# ATX_Power_Connector_Breakout.net
KiCad netlist of a schematic drawn in EAGLE
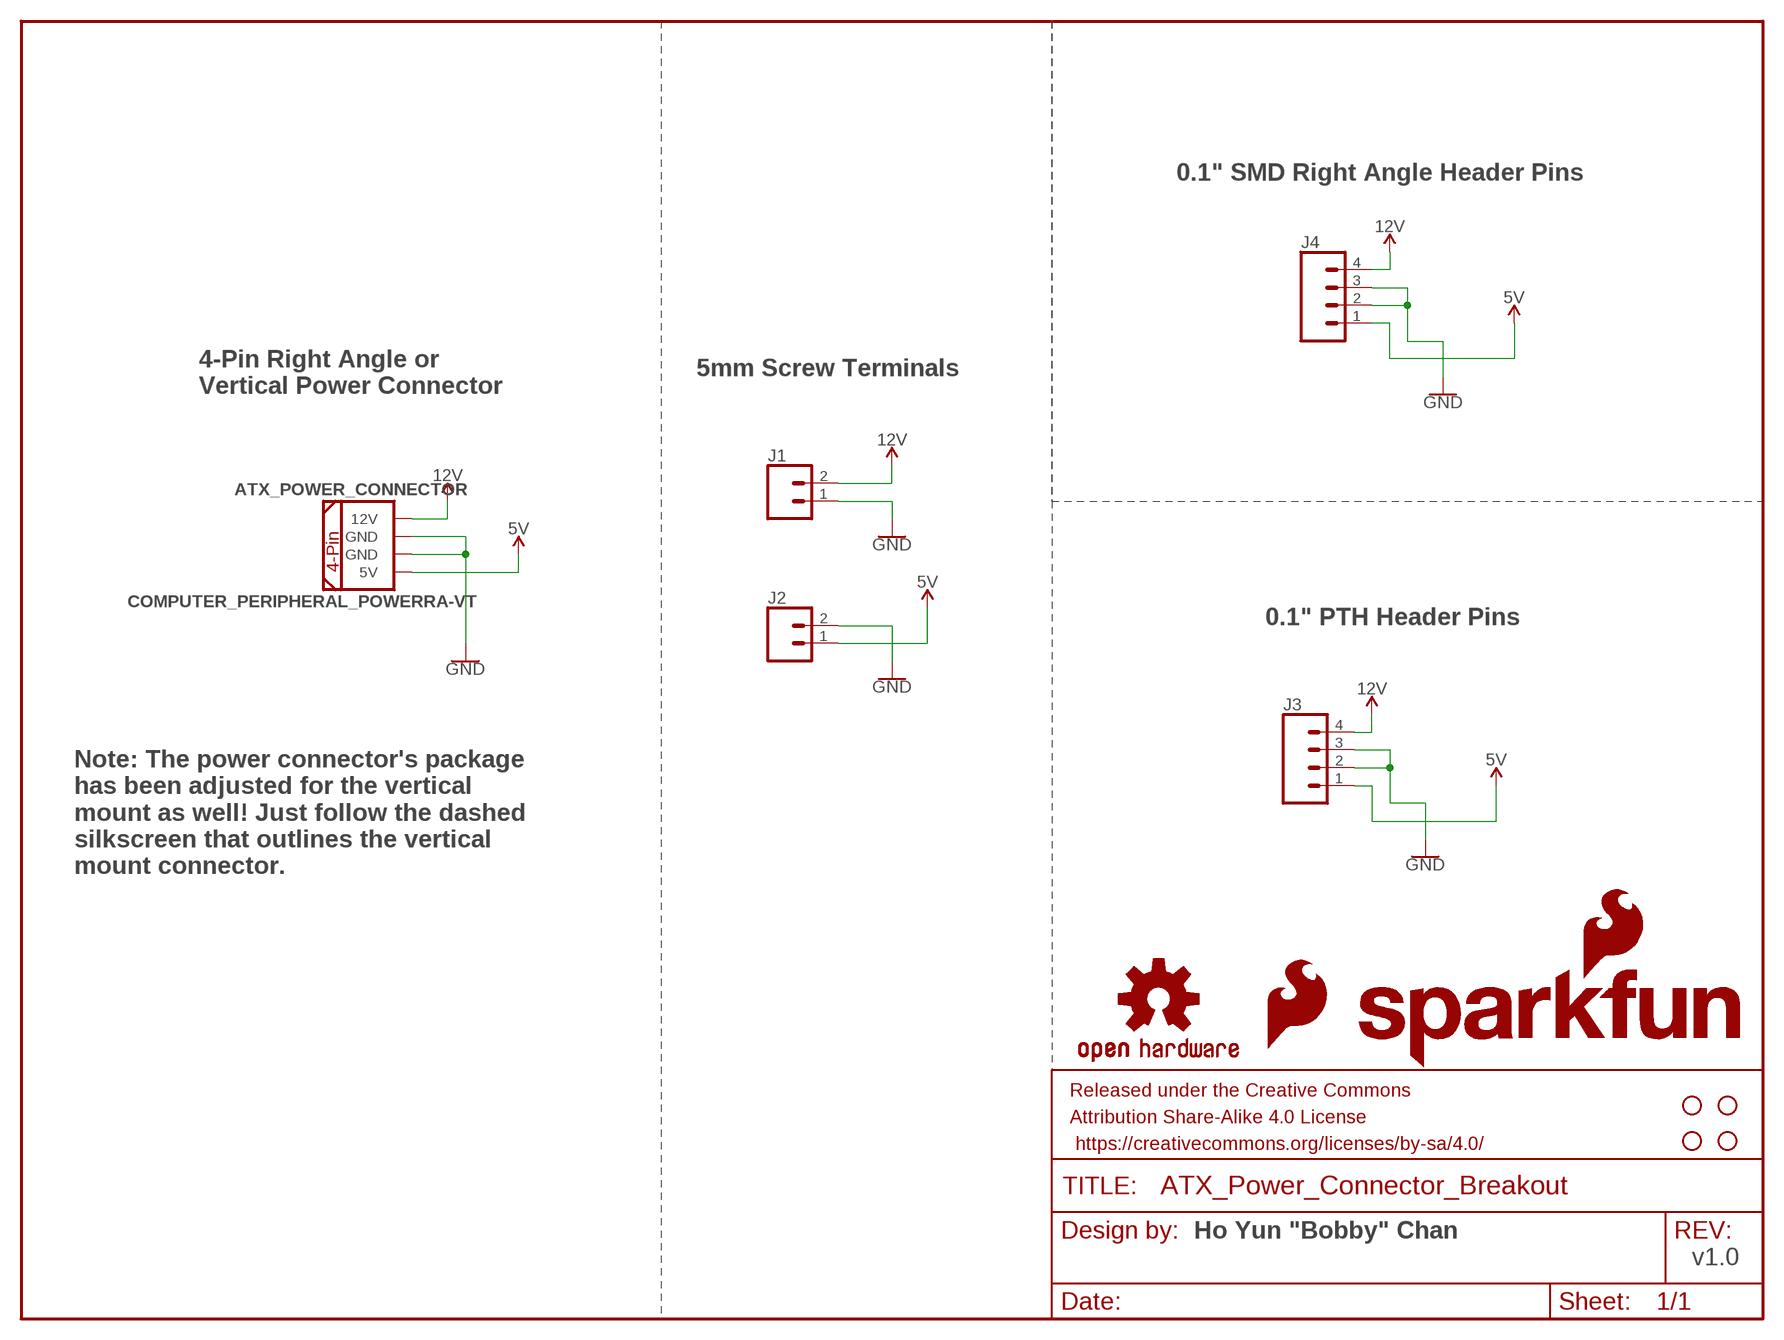
[diagram p0: schematic, sheet 1]

(export (version "E")
  (design (tool "Eeschema 10.0.6"))
  (components
    (comp (ref "ATX_POWER_CONNECTOR")
      (value "COMPUTER_PERIPHERAL_POWERRA-VT")
      (footprint "eagle-import:COMPUTER-PERIPHERAL-POWER-RA-VT")
      (libsource (lib "eagle-import") (part "COMPUTER_PERIPHERAL_POWERRA-VT"))
    )
    (comp (ref "FRAME1")
      (value "FRAME-LETTER")
      (footprint "eagle-import:CREATIVE_COMMONS")
      (libsource (lib "eagle-import") (part "FRAME-LETTER"))
    )
    (comp (ref "H1")
      (value "STAND-OFF")
      (footprint "eagle-import:STAND-OFF")
      (libsource (lib "eagle-import") (part "STAND-OFF"))
    )
    (comp (ref "H2")
      (value "STAND-OFF")
      (footprint "eagle-import:STAND-OFF")
      (libsource (lib "eagle-import") (part "STAND-OFF"))
    )
    (comp (ref "H3")
      (value "STAND-OFF")
      (footprint "eagle-import:STAND-OFF")
      (libsource (lib "eagle-import") (part "STAND-OFF"))
    )
    (comp (ref "H4")
      (value "STAND-OFF")
      (footprint "eagle-import:STAND-OFF")
      (libsource (lib "eagle-import") (part "STAND-OFF"))
    )
    (comp (ref "J1")
      (value "CONN_025MM")
      (footprint "eagle-import:SCREWTERMINAL-5MM-2")
      (libsource (lib "eagle-import") (part "CONN_025MM"))
    )
    (comp (ref "J2")
      (value "CONN_025MM")
      (footprint "eagle-import:SCREWTERMINAL-5MM-2")
      (libsource (lib "eagle-import") (part "CONN_025MM"))
    )
    (comp (ref "J3")
      (value "CONN_04")
      (footprint "eagle-import:1X04")
      (libsource (lib "eagle-import") (part "CONN_04"))
    )
    (comp (ref "J4")
      (value "CONN_04SMD")
      (footprint "eagle-import:1X04_SMD_RA_MALE")
      (libsource (lib "eagle-import") (part "CONN_04SMD"))
    )
    (comp (ref "LOGO1")
      (value "OSHW-LOGOS")
      (footprint "eagle-import:OSHW-LOGO-S")
      (libsource (lib "eagle-import") (part "OSHW-LOGOS"))
    )
    (comp (ref "LOGO2")
      (value "SFE_LOGO_NAME_FLAME.1_INCH")
      (footprint "eagle-import:SFE_LOGO_NAME_FLAME_.1")
      (libsource (lib "eagle-import") (part "SFE_LOGO_NAME_FLAME.1_INCH"))
    )
    (comp (ref "LOGO3")
      (value "SFE_LOGO_FLAME.1_INCH")
      (footprint "eagle-import:SFE_LOGO_FLAME_.1")
      (libsource (lib "eagle-import") (part "SFE_LOGO_FLAME.1_INCH"))
    )
  )
  (nets
    (net (code "1") (name "5V") (class "Default")
      (node (ref "ATX_POWER_CONNECTOR") (pin "5V") (pinfunction "5V_5V") (pintype "passive"))
      (node (ref "J2") (pin "1") (pinfunction "1_1") (pintype "passive"))
      (node (ref "J3") (pin "1") (pinfunction "1_1") (pintype "passive"))
      (node (ref "J4") (pin "1") (pinfunction "1_1") (pintype "passive"))
    )
    (net (code "2") (name "12V") (class "Default")
      (node (ref "ATX_POWER_CONNECTOR") (pin "12V") (pinfunction "12V_12V") (pintype "passive"))
      (node (ref "J1") (pin "2") (pinfunction "2_2") (pintype "passive"))
      (node (ref "J3") (pin "4") (pinfunction "4_4") (pintype "passive"))
      (node (ref "J4") (pin "4") (pinfunction "4_4") (pintype "passive"))
    )
    (net (code "3") (name "GND") (class "Default")
      (node (ref "ATX_POWER_CONNECTOR") (pin "GND@1") (pinfunction "GND_GND@1") (pintype "passive"))
      (node (ref "ATX_POWER_CONNECTOR") (pin "GND@2") (pinfunction "GND_GND@2") (pintype "passive"))
      (node (ref "J1") (pin "1") (pinfunction "1_1") (pintype "passive"))
      (node (ref "J2") (pin "2") (pinfunction "2_2") (pintype "passive"))
      (node (ref "J3") (pin "2") (pinfunction "2_2") (pintype "passive"))
      (node (ref "J3") (pin "3") (pinfunction "3_3") (pintype "passive"))
      (node (ref "J4") (pin "2") (pinfunction "2_2") (pintype "passive"))
      (node (ref "J4") (pin "3") (pinfunction "3_3") (pintype "passive"))
    )
  )
)
